# Battery_Board_rev_2.net
KiCad netlist of a schematic drawn in EAGLE
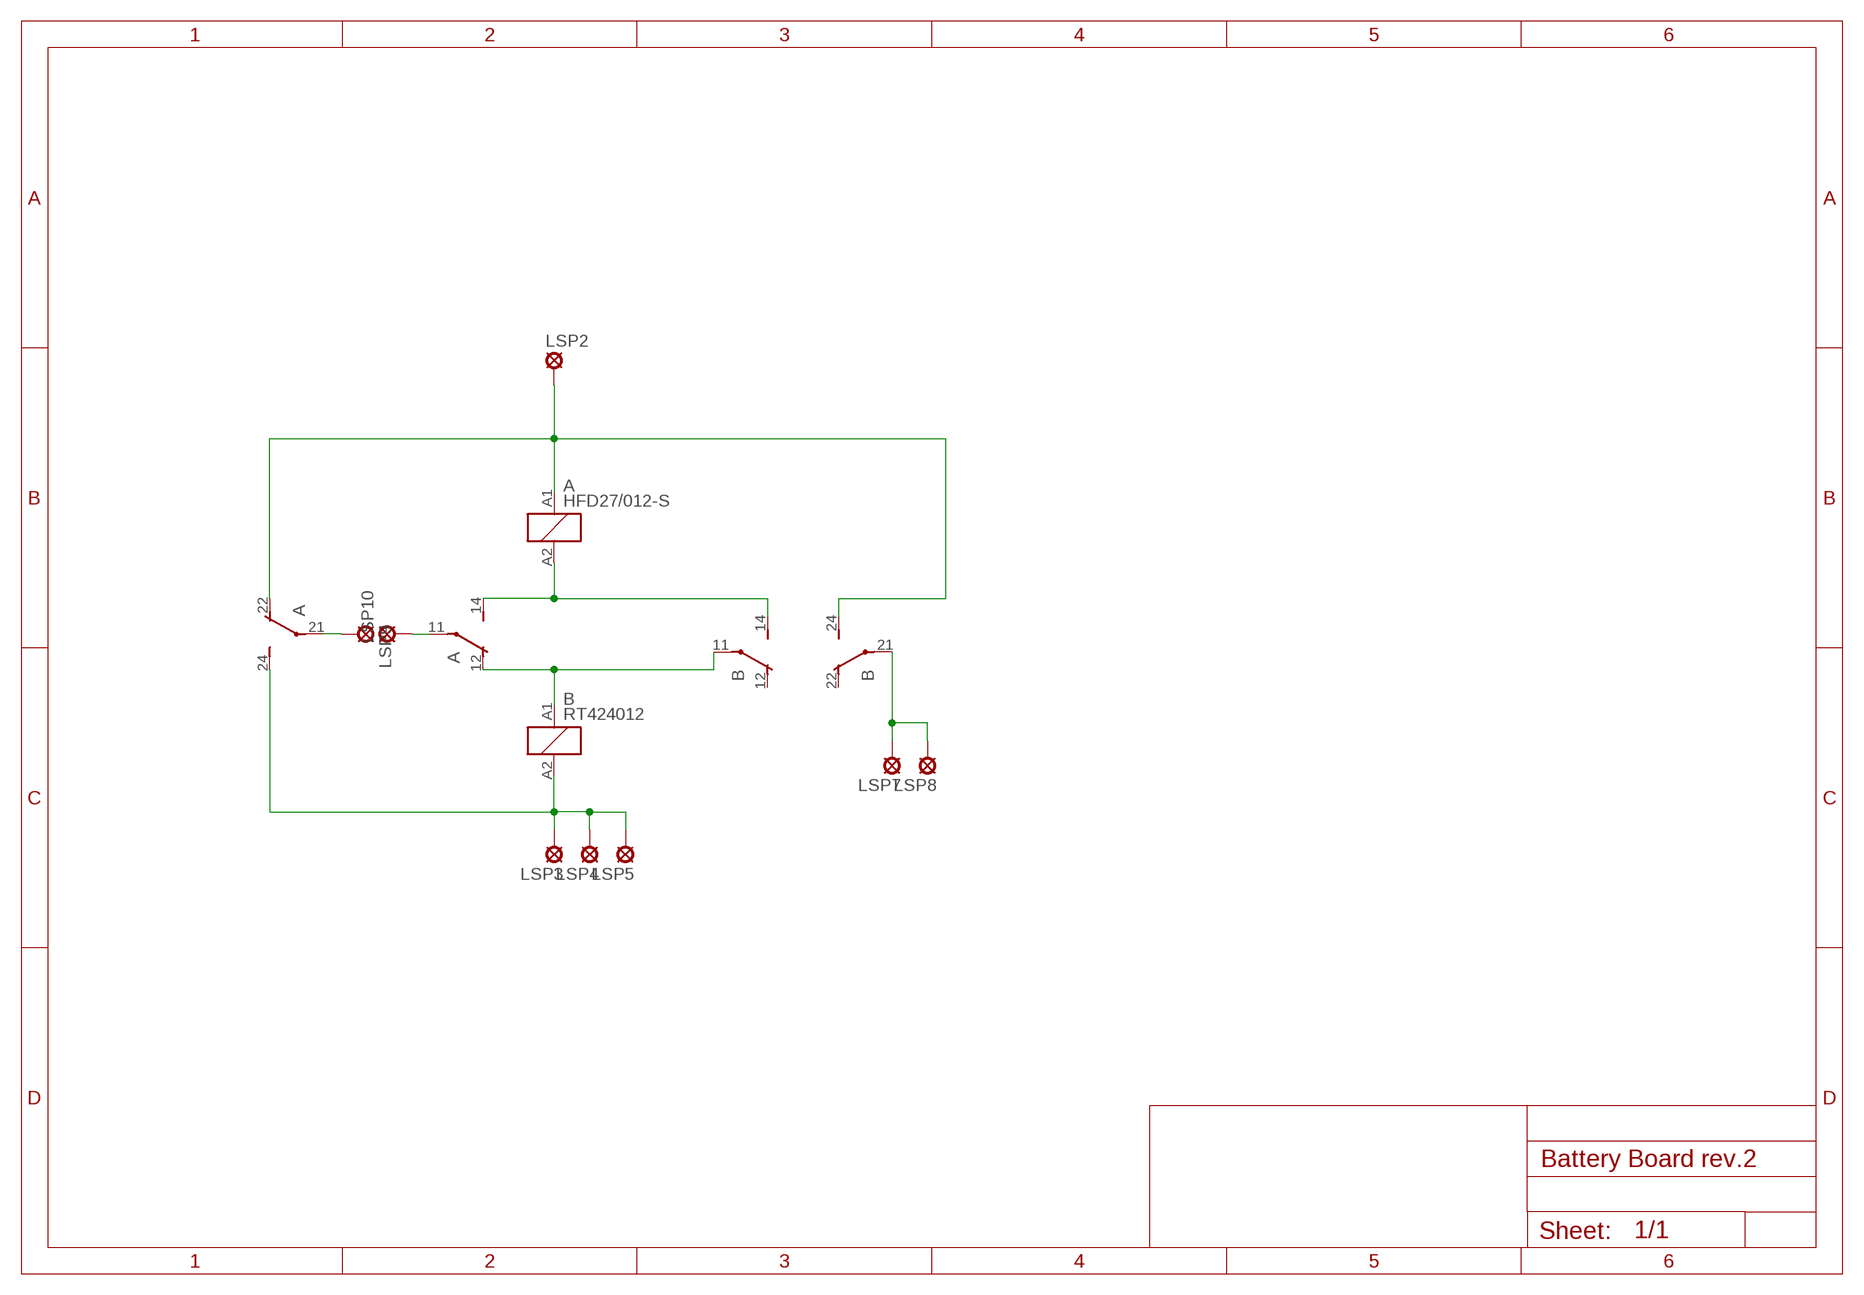
[diagram p0: schematic, sheet 1]

(export (version "E")
  (design (tool "Eeschema 10.0.6"))
  (components
    (comp (ref "A")
      (value "HFD27/012-S")
      (footprint "eagle-import:JRC27F")
      (libsource (lib "eagle-import") (part "HFD27/012-S"))
    )
    (comp (ref "B")
      (value "RT424012")
      (footprint "eagle-import:RT2C_O")
      (libsource (lib "eagle-import") (part "RT42?4012"))
    )
    (comp (ref "LSP2")
      (value "MCS08")
      (footprint "eagle-import:MCS08")
      (libsource (lib "eagle-import") (part "MCS08"))
    )
    (comp (ref "LSP3")
      (value "MCS08")
      (footprint "eagle-import:MCS08")
      (libsource (lib "eagle-import") (part "MCS08"))
    )
    (comp (ref "LSP4")
      (value "MCS08")
      (footprint "eagle-import:MCS08")
      (libsource (lib "eagle-import") (part "MCS08"))
    )
    (comp (ref "LSP5")
      (value "MCS08")
      (footprint "eagle-import:MCS08")
      (libsource (lib "eagle-import") (part "MCS08"))
    )
    (comp (ref "LSP7")
      (value "MCS08")
      (footprint "eagle-import:MCS08")
      (libsource (lib "eagle-import") (part "MCS08"))
    )
    (comp (ref "LSP8")
      (value "MCS08")
      (footprint "eagle-import:MCS08")
      (libsource (lib "eagle-import") (part "MCS08"))
    )
    (comp (ref "LSP9")
      (value "MCS08")
      (footprint "eagle-import:MCS08")
      (libsource (lib "eagle-import") (part "MCS08"))
    )
    (comp (ref "LSP10")
      (value "MCS08")
      (footprint "eagle-import:MCS08")
      (libsource (lib "eagle-import") (part "MCS08"))
    )
  )
  (nets
    (net (code "1") (name "Net-(AA-1)") (class "Default")
      (node (ref "A") (pin "22") (pinfunction "NC_22") (pintype "passive"))
      (node (ref "A") (pin "A1") (pinfunction "1_A1") (pintype "passive"))
      (node (ref "B") (pin "24") (pinfunction "S_24") (pintype "passive"))
      (node (ref "LSP2") (pin "MP") (pinfunction "MP_MP") (pintype "passive"))
    )
    (net (code "2") (name "Net-(AA-2)") (class "Default")
      (node (ref "A") (pin "14") (pinfunction "NO_14") (pintype "passive"))
      (node (ref "A") (pin "A2") (pinfunction "2_A2") (pintype "passive"))
      (node (ref "B") (pin "14") (pinfunction "S_14") (pintype "passive"))
    )
    (net (code "3") (name "Net-(AB-C)") (class "Default")
      (node (ref "A") (pin "11") (pinfunction "C_11") (pintype "passive"))
      (node (ref "LSP10") (pin "MP") (pinfunction "MP_MP") (pintype "passive"))
    )
    (net (code "4") (name "Net-(AB-NC)") (class "Default")
      (node (ref "A") (pin "12") (pinfunction "NC_12") (pintype "passive"))
      (node (ref "B") (pin "11") (pinfunction "P_11") (pintype "passive"))
      (node (ref "B") (pin "A1") (pinfunction "1_A1") (pintype "passive"))
    )
    (net (code "5") (name "Net-(AC-C)") (class "Default")
      (node (ref "A") (pin "21") (pinfunction "C_21") (pintype "passive"))
      (node (ref "LSP9") (pin "MP") (pinfunction "MP_MP") (pintype "passive"))
    )
    (net (code "6") (name "Net-(AC-NO)") (class "Default")
      (node (ref "A") (pin "24") (pinfunction "NO_24") (pintype "passive"))
      (node (ref "B") (pin "A2") (pinfunction "2_A2") (pintype "passive"))
      (node (ref "LSP3") (pin "MP") (pinfunction "MP_MP") (pintype "passive"))
      (node (ref "LSP4") (pin "MP") (pinfunction "MP_MP") (pintype "passive"))
      (node (ref "LSP5") (pin "MP") (pinfunction "MP_MP") (pintype "passive"))
    )
    (net (code "7") (name "Net-(BC-P)") (class "Default")
      (node (ref "B") (pin "21") (pinfunction "P_21") (pintype "passive"))
      (node (ref "LSP7") (pin "MP") (pinfunction "MP_MP") (pintype "passive"))
      (node (ref "LSP8") (pin "MP") (pinfunction "MP_MP") (pintype "passive"))
    )
    (net (code "8") (name "unconnected-(BB-O-Pad12)") (class "Default")
      (node (ref "B") (pin "12") (pinfunction "O_12") (pintype "passive"))
    )
    (net (code "9") (name "unconnected-(BC-O-Pad22)") (class "Default")
      (node (ref "B") (pin "22") (pinfunction "O_22") (pintype "passive"))
    )
  )
)
